# mainboard_v2_1.net
KiCad netlist of a schematic drawn in EAGLE
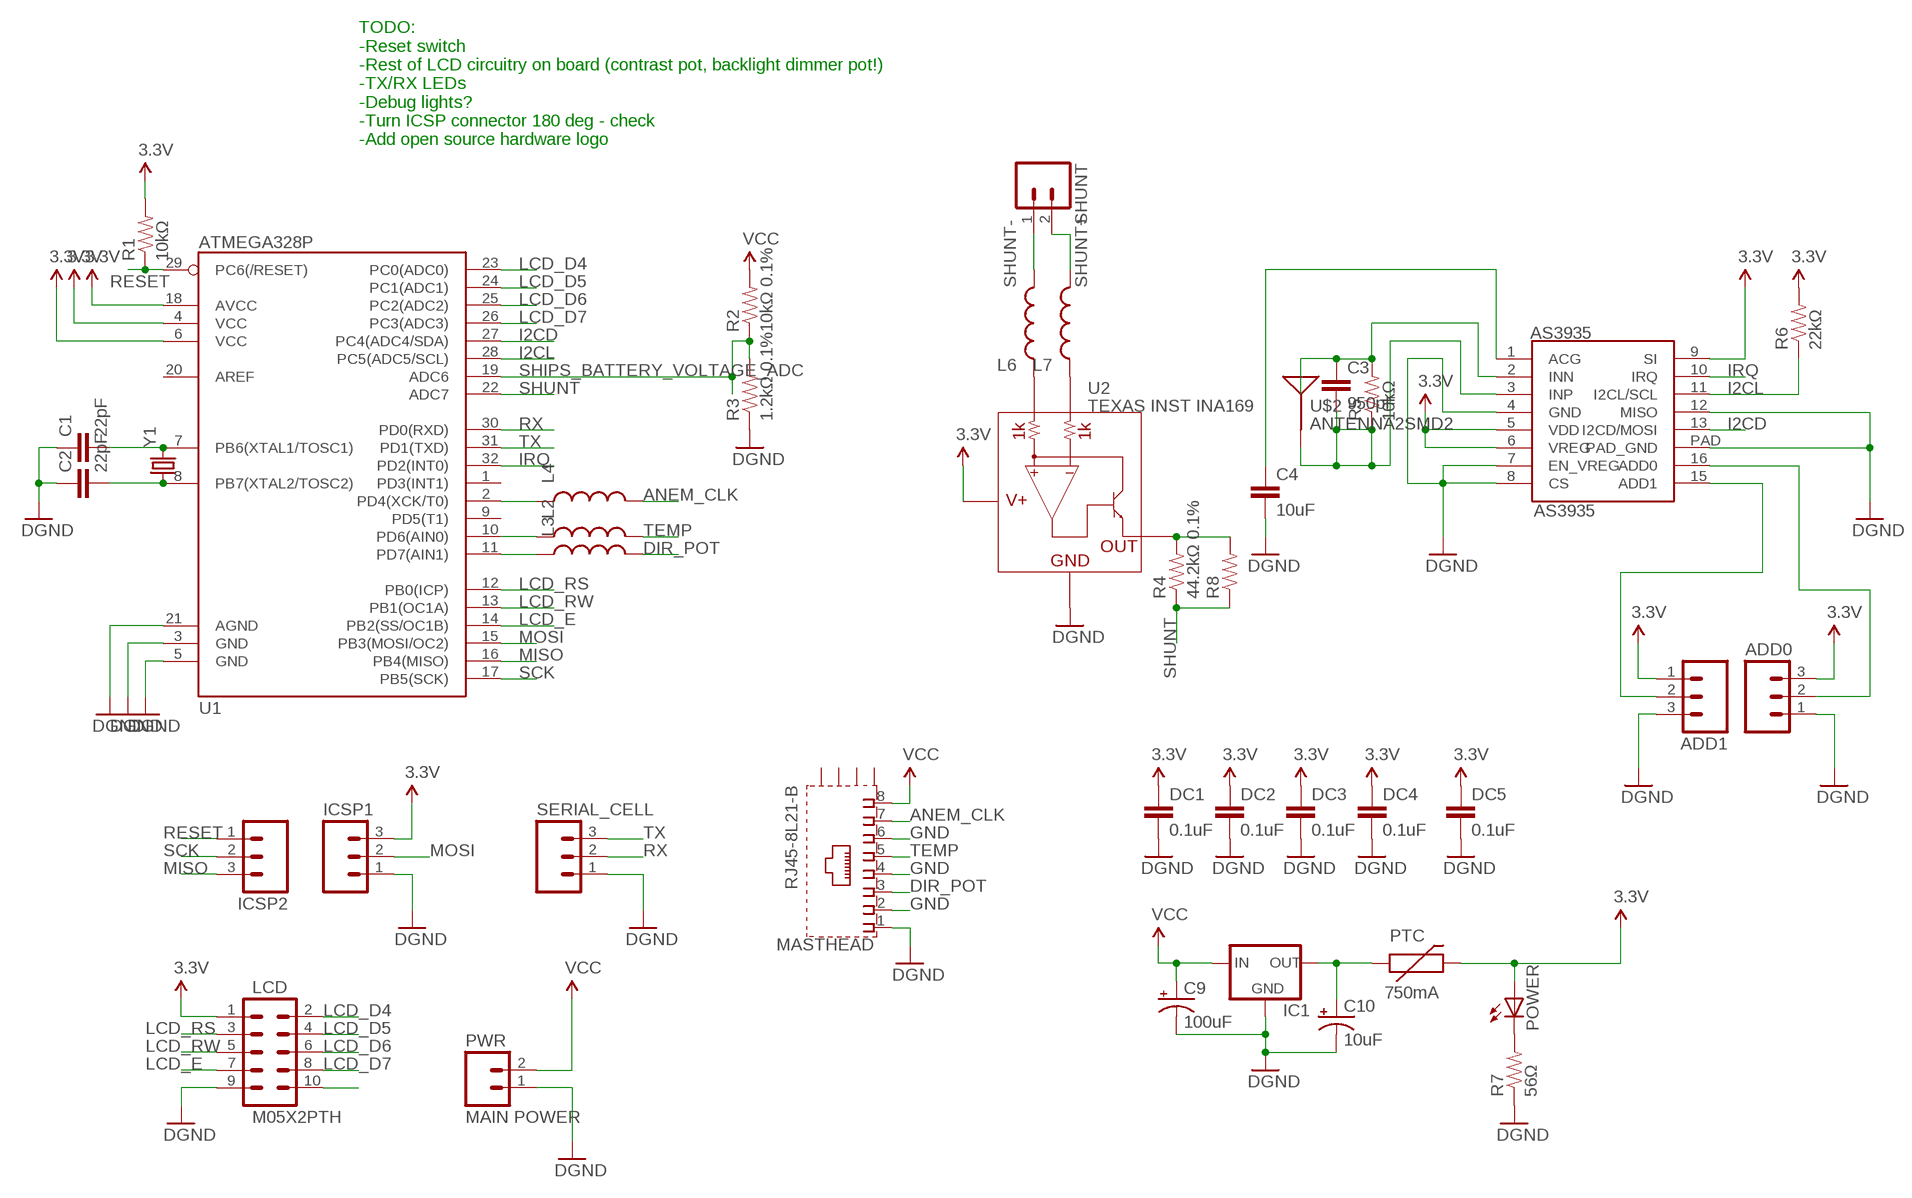
[diagram p0: schematic, sheet 1]

(export (version "E")
  (design (tool "Eeschema 10.0.6"))
  (components
    (comp (ref "ADD0")
      (value "M03LOCK")
      (footprint "eagle-import:1X03_LOCK")
      (libsource (lib "eagle-import") (part "M03LOCK"))
    )
    (comp (ref "ADD1")
      (value "M03LOCK")
      (footprint "eagle-import:1X03_LOCK")
      (libsource (lib "eagle-import") (part "M03LOCK"))
    )
    (comp (ref "AS3935")
      (value "AS3935")
      (footprint "eagle-import:16LDMLPQ")
      (libsource (lib "eagle-import") (part "AS3935"))
    )
    (comp (ref "C1")
      (value "22pF")
      (footprint "eagle-import:0805")
      (libsource (lib "eagle-import") (part "CAP0805"))
    )
    (comp (ref "C2")
      (value "22pF")
      (footprint "eagle-import:0805")
      (libsource (lib "eagle-import") (part "CAP0805"))
    )
    (comp (ref "C3")
      (value "950pF")
      (footprint "eagle-import:0805")
      (libsource (lib "eagle-import") (part "CAP0805"))
    )
    (comp (ref "C4")
      (value "10uF")
      (footprint "eagle-import:0805")
      (libsource (lib "eagle-import") (part "CAP0805"))
    )
    (comp (ref "C9")
      (value "100uF")
      (footprint "eagle-import:CPOL-RADIAL-1000UF-25V")
      (libsource (lib "eagle-import") (part "CAP_POLPTH4"))
    )
    (comp (ref "C10")
      (value "10uF")
      (footprint "eagle-import:CPOL-RADIAL-10UF-25V")
      (libsource (lib "eagle-import") (part "CAP_POLPTH2"))
    )
    (comp (ref "DC1")
      (value "0.1uF")
      (footprint "eagle-import:0805")
      (libsource (lib "eagle-import") (part "CAP0805"))
    )
    (comp (ref "DC2")
      (value "0.1uF")
      (footprint "eagle-import:0805")
      (libsource (lib "eagle-import") (part "CAP0805"))
    )
    (comp (ref "DC3")
      (value "0.1uF")
      (footprint "eagle-import:0805")
      (libsource (lib "eagle-import") (part "CAP0805"))
    )
    (comp (ref "DC4")
      (value "0.1uF")
      (footprint "eagle-import:0805")
      (libsource (lib "eagle-import") (part "CAP0805"))
    )
    (comp (ref "DC5")
      (value "0.1uF")
      (footprint "eagle-import:0805")
      (libsource (lib "eagle-import") (part "CAP0805"))
    )
    (comp (ref "IC1")
      (value "V_REG_78XXSINK")
      (footprint "eagle-import:TO220-IGO")
      (libsource (lib "eagle-import") (part "V_REG_78XXSINK"))
    )
    (comp (ref "ICSP1")
      (value "M03PTH")
      (footprint "eagle-import:1X03")
      (libsource (lib "eagle-import") (part "M03PTH"))
    )
    (comp (ref "ICSP2")
      (value "M03PTH")
      (footprint "eagle-import:1X03")
      (libsource (lib "eagle-import") (part "M03PTH"))
    )
    (comp (ref "L2")
      (value "INDUCTOR0805")
      (footprint "eagle-import:0805")
      (libsource (lib "eagle-import") (part "INDUCTOR0805"))
    )
    (comp (ref "L3")
      (value "INDUCTOR0805")
      (footprint "eagle-import:0805")
      (libsource (lib "eagle-import") (part "INDUCTOR0805"))
    )
    (comp (ref "L4")
      (value "INDUCTOR0805")
      (footprint "eagle-import:0805")
      (libsource (lib "eagle-import") (part "INDUCTOR0805"))
    )
    (comp (ref "L6")
      (value "INDUCTOR0805")
      (footprint "eagle-import:0805")
      (libsource (lib "eagle-import") (part "INDUCTOR0805"))
    )
    (comp (ref "L7")
      (value "INDUCTOR0805")
      (footprint "eagle-import:0805")
      (libsource (lib "eagle-import") (part "INDUCTOR0805"))
    )
    (comp (ref "LCD")
      (value "M05X2PTH")
      (footprint "eagle-import:AVR_ICSP")
      (libsource (lib "eagle-import") (part "M05X2PTH"))
    )
    (comp (ref "MASTHEAD")
      (value "RJ45-8L21-B")
      (footprint "eagle-import:RJ45-SHIELD1")
      (libsource (lib "eagle-import") (part "RJ4521-B-8L"))
    )
    (comp (ref "POWER")
      (value "LED1206")
      (footprint "eagle-import:LED-1206")
      (libsource (lib "eagle-import") (part "LED1206"))
    )
    (comp (ref "PTC")
      (value "750mA")
      (footprint "eagle-import:PTC-1206")
      (libsource (lib "eagle-import") (part "PTCSMD"))
    )
    (comp (ref "PWR")
      (value "MAIN POWER")
      (footprint "eagle-import:JST-2-PTH-NS")
      (libsource (lib "eagle-import") (part "M02-JST-2-PTH-NO_SILK"))
    )
    (comp (ref "R1")
      (value "10kΩ")
      (footprint "eagle-import:0805")
      (libsource (lib "eagle-import") (part "RESISTOR0805-RES"))
    )
    (comp (ref "R2")
      (value "10kΩ 0.1%")
      (footprint "eagle-import:0805")
      (libsource (lib "eagle-import") (part "RESISTOR0805-RES"))
    )
    (comp (ref "R3")
      (value "1.2kΩ 0.1%")
      (footprint "eagle-import:0805")
      (libsource (lib "eagle-import") (part "RESISTOR0805-RES"))
    )
    (comp (ref "R4")
      (value "44.2kΩ 0.1%")
      (footprint "eagle-import:0805")
      (libsource (lib "eagle-import") (part "RESISTOR0805-RES"))
    )
    (comp (ref "R5")
      (value "10kΩ")
      (footprint "eagle-import:0805")
      (libsource (lib "eagle-import") (part "RESISTOR0805-RES"))
    )
    (comp (ref "R6")
      (value "22kΩ")
      (footprint "eagle-import:0805")
      (libsource (lib "eagle-import") (part "RESISTOR0805-RES"))
    )
    (comp (ref "R7")
      (value "56Ω")
      (footprint "eagle-import:0805")
      (libsource (lib "eagle-import") (part "RESISTOR0805-RES"))
    )
    (comp (ref "R8")
      (value "RESISTOR0402-RES")
      (footprint "eagle-import:0402-RES")
      (libsource (lib "eagle-import") (part "RESISTOR0402-RES"))
    )
    (comp (ref "SERIAL_CELL")
      (value "M03LOCK")
      (footprint "eagle-import:1X03_LOCK")
      (libsource (lib "eagle-import") (part "M03LOCK"))
    )
    (comp (ref "SHUNT")
      (value "M02LOCK")
      (footprint "eagle-import:1X02_LOCK")
      (libsource (lib "eagle-import") (part "M02LOCK"))
    )
    (comp (ref "U$2")
      (value "ANTENNA2SMD2")
      (footprint "eagle-import:ANTENNA-CHIP3")
      (libsource (lib "eagle-import") (part "ANTENNA2SMD2"))
    )
    (comp (ref "U1")
      (value "ATMEGA328P")
      (footprint "eagle-import:TQFP32-08")
      (libsource (lib "eagle-import") (part "ATMEGA328_SMT"))
    )
    (comp (ref "U2")
      (value "TEXAS INST INA169")
      (footprint "eagle-import:SOT23-5")
      (libsource (lib "eagle-import") (part "INA139"))
    )
    (comp (ref "Y1")
      (value "CRYSTALTXC-7A")
      (footprint "eagle-import:CRYSTAL-TXC-7A")
      (libsource (lib "eagle-import") (part "CRYSTALTXC-7A"))
    )
  )
  (nets
    (net (code "1") (name "/ANEM_CLK") (class "Default")
      (node (ref "L4") (pin "2") (pinfunction "2_2") (pintype "passive"))
      (node (ref "MASTHEAD") (pin "7") (pinfunction "7_7") (pintype "passive"))
    )
    (net (code "2") (name "/DIR_POT") (class "Default")
      (node (ref "L3") (pin "2") (pinfunction "2_2") (pintype "passive"))
      (node (ref "MASTHEAD") (pin "3") (pinfunction "3_3") (pintype "passive"))
    )
    (net (code "3") (name "/I2CD") (class "Default")
      (node (ref "AS3935") (pin "13") (pinfunction "I2CD/MOSI_13") (pintype "bidirectional"))
      (node (ref "U1") (pin "27") (pinfunction "PC4(ADC4/SDA)_27") (pintype "bidirectional"))
    )
    (net (code "4") (name "/I2CL") (class "Default")
      (node (ref "AS3935") (pin "11") (pinfunction "I2CL/SCL_11") (pintype "bidirectional"))
      (node (ref "R6") (pin "1") (pinfunction "1_1") (pintype "passive"))
      (node (ref "U1") (pin "28") (pinfunction "PC5(ADC5/SCL)_28") (pintype "bidirectional"))
    )
    (net (code "5") (name "/IRQ") (class "Default")
      (node (ref "AS3935") (pin "10") (pinfunction "IRQ_10") (pintype "bidirectional"))
      (node (ref "U1") (pin "32") (pinfunction "PD2(INT0)_32") (pintype "bidirectional"))
    )
    (net (code "6") (name "/LCD_D4") (class "Default")
      (node (ref "LCD") (pin "2") (pinfunction "2_2") (pintype "passive"))
      (node (ref "U1") (pin "23") (pinfunction "PC0(ADC0)_23") (pintype "bidirectional"))
    )
    (net (code "7") (name "/LCD_D5") (class "Default")
      (node (ref "LCD") (pin "4") (pinfunction "4_4") (pintype "passive"))
      (node (ref "U1") (pin "24") (pinfunction "PC1(ADC1)_24") (pintype "bidirectional"))
    )
    (net (code "8") (name "/LCD_D6") (class "Default")
      (node (ref "LCD") (pin "6") (pinfunction "6_6") (pintype "passive"))
      (node (ref "U1") (pin "25") (pinfunction "PC2(ADC2)_25") (pintype "bidirectional"))
    )
    (net (code "9") (name "/LCD_D7") (class "Default")
      (node (ref "LCD") (pin "8") (pinfunction "8_8") (pintype "passive"))
      (node (ref "U1") (pin "26") (pinfunction "PC3(ADC3)_26") (pintype "bidirectional"))
    )
    (net (code "10") (name "/LCD_E") (class "Default")
      (node (ref "LCD") (pin "7") (pinfunction "7_7") (pintype "passive"))
      (node (ref "U1") (pin "14") (pinfunction "PB2(SS/OC1B)_14") (pintype "bidirectional"))
    )
    (net (code "11") (name "/LCD_RS") (class "Default")
      (node (ref "LCD") (pin "3") (pinfunction "3_3") (pintype "passive"))
      (node (ref "U1") (pin "12") (pinfunction "PB0(ICP)_12") (pintype "bidirectional"))
    )
    (net (code "12") (name "/LCD_RW") (class "Default")
      (node (ref "LCD") (pin "5") (pinfunction "5_5") (pintype "passive"))
      (node (ref "U1") (pin "13") (pinfunction "PB1(OC1A)_13") (pintype "bidirectional"))
    )
    (net (code "13") (name "/MISO") (class "Default")
      (node (ref "ICSP2") (pin "3") (pinfunction "3_3") (pintype "passive"))
      (node (ref "U1") (pin "16") (pinfunction "PB4(MISO)_16") (pintype "bidirectional"))
    )
    (net (code "14") (name "/MOSI") (class "Default")
      (node (ref "ICSP1") (pin "2") (pinfunction "2_2") (pintype "passive"))
      (node (ref "U1") (pin "15") (pinfunction "PB3(MOSI/OC2)_15") (pintype "bidirectional"))
    )
    (net (code "15") (name "/RESET") (class "Default")
      (node (ref "ICSP2") (pin "1") (pinfunction "1_1") (pintype "passive"))
      (node (ref "R1") (pin "1") (pinfunction "1_1") (pintype "passive"))
      (node (ref "U1") (pin "29") (pinfunction "PC6(/RESET)_29") (pintype "bidirectional"))
    )
    (net (code "16") (name "/RX") (class "Default")
      (node (ref "SERIAL_CELL") (pin "2") (pinfunction "2_2") (pintype "passive"))
      (node (ref "U1") (pin "30") (pinfunction "PD0(RXD)_30") (pintype "bidirectional"))
    )
    (net (code "17") (name "/SCK") (class "Default")
      (node (ref "ICSP2") (pin "2") (pinfunction "2_2") (pintype "passive"))
      (node (ref "U1") (pin "17") (pinfunction "PB5(SCK)_17") (pintype "bidirectional"))
    )
    (net (code "18") (name "/SHIPS_BATTERY_VOLTAGE_ADC") (class "Default")
      (node (ref "R2") (pin "1") (pinfunction "1_1") (pintype "passive"))
      (node (ref "R3") (pin "2") (pinfunction "2_2") (pintype "passive"))
      (node (ref "U1") (pin "19") (pinfunction "ADC6_19") (pintype "bidirectional"))
    )
    (net (code "19") (name "/SHUNT") (class "Default")
      (node (ref "R4") (pin "1") (pinfunction "1_1") (pintype "passive"))
      (node (ref "R8") (pin "1") (pinfunction "1_1") (pintype "passive"))
      (node (ref "U1") (pin "22") (pinfunction "ADC7_22") (pintype "bidirectional"))
    )
    (net (code "20") (name "/SHUNT+") (class "Default")
      (node (ref "L7") (pin "2") (pinfunction "2_2") (pintype "passive"))
      (node (ref "SHUNT") (pin "2") (pinfunction "2_2") (pintype "passive"))
    )
    (net (code "21") (name "/SHUNT-") (class "Default")
      (node (ref "L6") (pin "2") (pinfunction "2_2") (pintype "passive"))
      (node (ref "SHUNT") (pin "1") (pinfunction "1_1") (pintype "passive"))
    )
    (net (code "22") (name "/TEMP") (class "Default")
      (node (ref "L2") (pin "2") (pinfunction "2_2") (pintype "passive"))
      (node (ref "MASTHEAD") (pin "5") (pinfunction "5_5") (pintype "passive"))
    )
    (net (code "23") (name "/TX") (class "Default")
      (node (ref "SERIAL_CELL") (pin "3") (pinfunction "3_3") (pintype "passive"))
      (node (ref "U1") (pin "31") (pinfunction "PD1(TXD)_31") (pintype "bidirectional"))
    )
    (net (code "24") (name "3.3V") (class "Default")
      (node (ref "ADD0") (pin "3") (pinfunction "3_3") (pintype "passive"))
      (node (ref "ADD1") (pin "1") (pinfunction "1_1") (pintype "passive"))
      (node (ref "AS3935") (pin "5") (pinfunction "VDD_5") (pintype "bidirectional"))
      (node (ref "AS3935") (pin "6") (pinfunction "VREG_6") (pintype "bidirectional"))
      (node (ref "AS3935") (pin "9") (pinfunction "SI_9") (pintype "bidirectional"))
      (node (ref "DC1") (pin "1") (pinfunction "1_1") (pintype "passive"))
      (node (ref "DC2") (pin "1") (pinfunction "1_1") (pintype "passive"))
      (node (ref "DC3") (pin "1") (pinfunction "1_1") (pintype "passive"))
      (node (ref "DC4") (pin "1") (pinfunction "1_1") (pintype "passive"))
      (node (ref "DC5") (pin "1") (pinfunction "1_1") (pintype "passive"))
      (node (ref "ICSP1") (pin "3") (pinfunction "3_3") (pintype "passive"))
      (node (ref "LCD") (pin "1") (pinfunction "1_1") (pintype "passive"))
      (node (ref "POWER") (pin "A") (pinfunction "A_A") (pintype "passive"))
      (node (ref "PTC") (pin "2") (pinfunction "2_2") (pintype "bidirectional"))
      (node (ref "R1") (pin "2") (pinfunction "2_2") (pintype "passive"))
      (node (ref "R6") (pin "2") (pinfunction "2_2") (pintype "passive"))
      (node (ref "U1") (pin "18") (pinfunction "AVCC_18") (pintype "bidirectional"))
      (node (ref "U1") (pin "4") (pinfunction "VCC_4") (pintype "bidirectional"))
      (node (ref "U1") (pin "6") (pinfunction "VCC_6") (pintype "bidirectional"))
      (node (ref "U2") (pin "5") (pinfunction "V+_5") (pintype "bidirectional"))
    )
    (net (code "25") (name "DGND") (class "Default")
      (node (ref "ADD0") (pin "1") (pinfunction "1_1") (pintype "passive"))
      (node (ref "ADD1") (pin "3") (pinfunction "3_3") (pintype "passive"))
      (node (ref "AS3935") (pin "12") (pinfunction "MISO_12") (pintype "bidirectional"))
      (node (ref "AS3935") (pin "4") (pinfunction "GND_4") (pintype "bidirectional"))
      (node (ref "AS3935") (pin "7") (pinfunction "EN_VREG_7") (pintype "bidirectional"))
      (node (ref "AS3935") (pin "8") (pinfunction "CS_8") (pintype "bidirectional"))
      (node (ref "AS3935") (pin "PAD") (pinfunction "PAD_GND_PAD") (pintype "bidirectional"))
      (node (ref "C1") (pin "1") (pinfunction "1_1") (pintype "passive"))
      (node (ref "C10") (pin "2") (pinfunction "-_2") (pintype "passive"))
      (node (ref "C2") (pin "1") (pinfunction "1_1") (pintype "passive"))
      (node (ref "C4") (pin "2") (pinfunction "2_2") (pintype "passive"))
      (node (ref "C9") (pin "2") (pinfunction "-_2") (pintype "passive"))
      (node (ref "DC1") (pin "2") (pinfunction "2_2") (pintype "passive"))
      (node (ref "DC2") (pin "2") (pinfunction "2_2") (pintype "passive"))
      (node (ref "DC3") (pin "2") (pinfunction "2_2") (pintype "passive"))
      (node (ref "DC4") (pin "2") (pinfunction "2_2") (pintype "passive"))
      (node (ref "DC5") (pin "2") (pinfunction "2_2") (pintype "passive"))
      (node (ref "IC1") (pin "GND") (pinfunction "GND_GND") (pintype "input"))
      (node (ref "ICSP1") (pin "1") (pinfunction "1_1") (pintype "passive"))
      (node (ref "LCD") (pin "9") (pinfunction "9_9") (pintype "passive"))
      (node (ref "MASTHEAD") (pin "1") (pinfunction "1_1") (pintype "passive"))
      (node (ref "MASTHEAD") (pin "2") (pinfunction "2_2") (pintype "passive"))
      (node (ref "MASTHEAD") (pin "4") (pinfunction "4_4") (pintype "passive"))
      (node (ref "MASTHEAD") (pin "6") (pinfunction "6_6") (pintype "passive"))
      (node (ref "PWR") (pin "1") (pinfunction "1_1") (pintype "passive"))
      (node (ref "R3") (pin "1") (pinfunction "1_1") (pintype "passive"))
      (node (ref "R7") (pin "1") (pinfunction "1_1") (pintype "passive"))
      (node (ref "SERIAL_CELL") (pin "1") (pinfunction "1_1") (pintype "passive"))
      (node (ref "U1") (pin "21") (pinfunction "AGND_21") (pintype "bidirectional"))
      (node (ref "U1") (pin "3") (pinfunction "GND_3") (pintype "bidirectional"))
      (node (ref "U1") (pin "5") (pinfunction "GND_5") (pintype "bidirectional"))
      (node (ref "U2") (pin "2") (pinfunction "GND_2") (pintype "bidirectional"))
    )
    (net (code "26") (name "Net-(AS3935-ACG)") (class "Default")
      (node (ref "AS3935") (pin "1") (pinfunction "ACG_1") (pintype "bidirectional"))
      (node (ref "C4") (pin "1") (pinfunction "1_1") (pintype "passive"))
    )
    (net (code "27") (name "Net-(AS3935-ADD0)") (class "Default")
      (node (ref "ADD0") (pin "2") (pinfunction "2_2") (pintype "passive"))
      (node (ref "AS3935") (pin "16") (pinfunction "ADD0_16") (pintype "bidirectional"))
    )
    (net (code "28") (name "Net-(AS3935-ADD1)") (class "Default")
      (node (ref "ADD1") (pin "2") (pinfunction "2_2") (pintype "passive"))
      (node (ref "AS3935") (pin "15") (pinfunction "ADD1_15") (pintype "bidirectional"))
    )
    (net (code "29") (name "Net-(AS3935-INN)") (class "Default")
      (node (ref "AS3935") (pin "2") (pinfunction "INN_2") (pintype "bidirectional"))
      (node (ref "C3") (pin "1") (pinfunction "1_1") (pintype "passive"))
      (node (ref "R5") (pin "2") (pinfunction "2_2") (pintype "passive"))
    )
    (net (code "30") (name "Net-(AS3935-INP)") (class "Default")
      (node (ref "AS3935") (pin "3") (pinfunction "INP_3") (pintype "bidirectional"))
      (node (ref "C3") (pin "2") (pinfunction "2_2") (pintype "passive"))
      (node (ref "R5") (pin "1") (pinfunction "1_1") (pintype "passive"))
      (node (ref "U$2") (pin "FEED") (pinfunction "SIGNAL_FEED") (pintype "bidirectional"))
    )
    (net (code "31") (name "Net-(C10-+)") (class "Default")
      (node (ref "C10") (pin "1") (pinfunction "+_1") (pintype "passive"))
      (node (ref "IC1") (pin "OUT") (pinfunction "OUT_OUT") (pintype "output"))
      (node (ref "PTC") (pin "1") (pinfunction "1_1") (pintype "bidirectional"))
    )
    (net (code "32") (name "Net-(POWER-PadC)") (class "Default")
      (node (ref "POWER") (pin "C") (pinfunction "C_C") (pintype "passive"))
      (node (ref "R7") (pin "2") (pinfunction "2_2") (pintype "passive"))
    )
    (net (code "33") (name "Net-(U1-PB6(XTAL1{slash}TOSC1))") (class "Default")
      (node (ref "C1") (pin "2") (pinfunction "2_2") (pintype "passive"))
      (node (ref "U1") (pin "7") (pinfunction "PB6(XTAL1/TOSC1)_7") (pintype "bidirectional"))
      (node (ref "Y1") (pin "P$2") (pinfunction "2_P$2") (pintype "passive"))
    )
    (net (code "34") (name "Net-(U1-PB7(XTAL2{slash}TOSC2))") (class "Default")
      (node (ref "C2") (pin "2") (pinfunction "2_2") (pintype "passive"))
      (node (ref "U1") (pin "8") (pinfunction "PB7(XTAL2/TOSC2)_8") (pintype "bidirectional"))
      (node (ref "Y1") (pin "P$1") (pinfunction "1_P$1") (pintype "passive"))
    )
    (net (code "35") (name "Net-(U1-PD4(XCK{slash}T0))") (class "Default")
      (node (ref "L4") (pin "1") (pinfunction "1_1") (pintype "passive"))
      (node (ref "U1") (pin "2") (pinfunction "PD4(XCK/T0)_2") (pintype "bidirectional"))
    )
    (net (code "36") (name "Net-(U1-PD6(AIN0))") (class "Default")
      (node (ref "L2") (pin "1") (pinfunction "1_1") (pintype "passive"))
      (node (ref "U1") (pin "10") (pinfunction "PD6(AIN0)_10") (pintype "bidirectional"))
    )
    (net (code "37") (name "Net-(U1-PD7(AIN1))") (class "Default")
      (node (ref "L3") (pin "1") (pinfunction "1_1") (pintype "passive"))
      (node (ref "U1") (pin "11") (pinfunction "PD7(AIN1)_11") (pintype "bidirectional"))
    )
    (net (code "38") (name "Net-(U2-OUT)") (class "Default")
      (node (ref "R4") (pin "2") (pinfunction "2_2") (pintype "passive"))
      (node (ref "R8") (pin "2") (pinfunction "2_2") (pintype "passive"))
      (node (ref "U2") (pin "1") (pinfunction "OUT_1") (pintype "bidirectional"))
    )
    (net (code "39") (name "Net-(U2-VIN+)") (class "Default")
      (node (ref "L6") (pin "1") (pinfunction "1_1") (pintype "passive"))
      (node (ref "U2") (pin "3") (pinfunction "VIN+_3") (pintype "bidirectional"))
    )
    (net (code "40") (name "Net-(U2-VIN-)") (class "Default")
      (node (ref "L7") (pin "1") (pinfunction "1_1") (pintype "passive"))
      (node (ref "U2") (pin "4") (pinfunction "VIN-_4") (pintype "bidirectional"))
    )
    (net (code "41") (name "VCC") (class "Default")
      (node (ref "C9") (pin "1") (pinfunction "+_1") (pintype "passive"))
      (node (ref "IC1") (pin "IN") (pinfunction "IN_IN") (pintype "input"))
      (node (ref "MASTHEAD") (pin "8") (pinfunction "8_8") (pintype "passive"))
      (node (ref "PWR") (pin "2") (pinfunction "2_2") (pintype "passive"))
      (node (ref "R2") (pin "2") (pinfunction "2_2") (pintype "passive"))
    )
    (net (code "42") (name "unconnected-(LCD-Pad10)") (class "Default")
      (node (ref "LCD") (pin "10") (pinfunction "10_10") (pintype "passive"))
    )
    (net (code "43") (name "unconnected-(MASTHEAD-S-PadS1)") (class "Default")
      (node (ref "MASTHEAD") (pin "S1") (pinfunction "S_S1") (pintype "passive"))
    )
    (net (code "44") (name "unconnected-(MASTHEAD-S-PadS2)") (class "Default")
      (node (ref "MASTHEAD") (pin "S2") (pinfunction "S_S2") (pintype "passive"))
    )
    (net (code "45") (name "unconnected-(MASTHEAD-S-PadS3)") (class "Default")
      (node (ref "MASTHEAD") (pin "S3") (pinfunction "S_S3") (pintype "passive"))
    )
    (net (code "46") (name "unconnected-(MASTHEAD-S-PadS4)") (class "Default")
      (node (ref "MASTHEAD") (pin "S4") (pinfunction "S_S4") (pintype "passive"))
    )
    (net (code "47") (name "unconnected-(U1-AREF-Pad20)") (class "Default")
      (node (ref "U1") (pin "20") (pinfunction "AREF_20") (pintype "bidirectional"))
    )
    (net (code "48") (name "unconnected-(U1-PD3(INT1)-Pad1)") (class "Default")
      (node (ref "U1") (pin "1") (pinfunction "PD3(INT1)_1") (pintype "bidirectional"))
    )
    (net (code "49") (name "unconnected-(U1-PD5(T1)-Pad9)") (class "Default")
      (node (ref "U1") (pin "9") (pinfunction "PD5(T1)_9") (pintype "bidirectional"))
    )
  )
)
